# LEDDriver_v_7.net
KiCad netlist of a schematic drawn in EAGLE
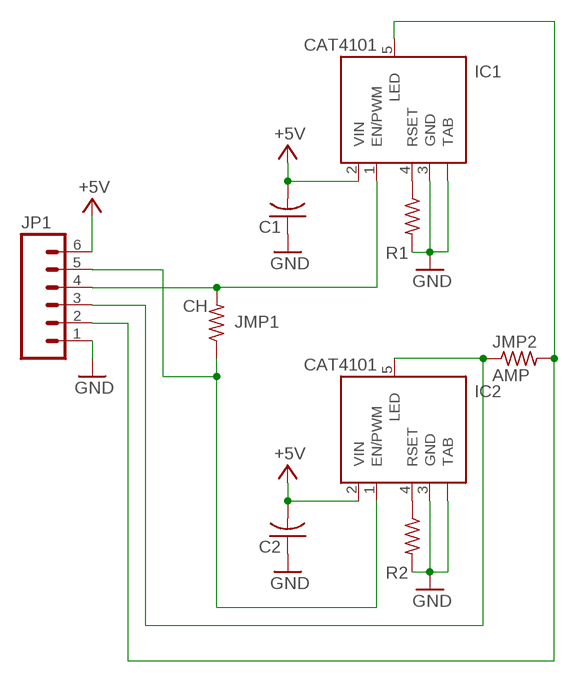
[diagram p0: schematic, sheet 1]

(export (version "E")
  (design (tool "Eeschema 10.0.6"))
  (components
    (comp (ref "C1")
      (value "C-USC1206")
      (footprint "eagle-import:C1206")
      (libsource (lib "eagle-import") (part "C-USC1206"))
    )
    (comp (ref "C2")
      (value "C-USC1206")
      (footprint "eagle-import:C1206")
      (libsource (lib "eagle-import") (part "C-USC1206"))
    )
    (comp (ref "IC1")
      (value "CAT4101")
      (footprint "eagle-import:TO263_5")
      (fields (field (name "MPN") "CAT4101TV-T75"))
      (libsource (lib "eagle-import") (part "CAT4101"))
    )
    (comp (ref "IC2")
      (value "CAT4101")
      (footprint "eagle-import:TO263_5")
      (fields (field (name "MPN") "CAT4101TV-T75"))
      (libsource (lib "eagle-import") (part "CAT4101"))
    )
    (comp (ref "JMP1")
      (value "CH")
      (footprint "eagle-import:R1206")
      (libsource (lib "eagle-import") (part "R-US_R1206"))
    )
    (comp (ref "JMP2")
      (value "AMP")
      (footprint "eagle-import:R1206")
      (libsource (lib "eagle-import") (part "R-US_R1206"))
    )
    (comp (ref "JP1")
      (value "M06LOCK_LONGPADS")
      (footprint "eagle-import:1X06_LOCK_LONGPADS")
      (libsource (lib "eagle-import") (part "M06LOCK_LONGPADS"))
    )
    (comp (ref "R1")
      (value "R-US_R1206")
      (footprint "eagle-import:R1206")
      (libsource (lib "eagle-import") (part "R-US_R1206"))
    )
    (comp (ref "R2")
      (value "R-US_R1206")
      (footprint "eagle-import:R1206")
      (libsource (lib "eagle-import") (part "R-US_R1206"))
    )
  )
  (nets
    (net (code "1") (name "+5V") (class "Default")
      (node (ref "C1") (pin "2") (pinfunction "2_2") (pintype "passive"))
      (node (ref "C2") (pin "2") (pinfunction "2_2") (pintype "passive"))
      (node (ref "IC1") (pin "2") (pinfunction "VIN_2") (pintype "input"))
      (node (ref "IC2") (pin "2") (pinfunction "VIN_2") (pintype "input"))
      (node (ref "JP1") (pin "6") (pinfunction "6_6") (pintype "passive"))
    )
    (net (code "2") (name "GND") (class "Default")
      (node (ref "C1") (pin "1") (pinfunction "1_1") (pintype "passive"))
      (node (ref "C2") (pin "1") (pinfunction "1_1") (pintype "passive"))
      (node (ref "IC1") (pin "3") (pinfunction "GND_3") (pintype "power_in"))
      (node (ref "IC1") (pin "TAB") (pinfunction "TAB_TAB") (pintype "passive"))
      (node (ref "IC2") (pin "3") (pinfunction "GND_3") (pintype "power_in"))
      (node (ref "IC2") (pin "TAB") (pinfunction "TAB_TAB") (pintype "passive"))
      (node (ref "JP1") (pin "1") (pinfunction "1_1") (pintype "passive"))
      (node (ref "R1") (pin "2") (pinfunction "2_2") (pintype "passive"))
      (node (ref "R2") (pin "2") (pinfunction "2_2") (pintype "passive"))
    )
    (net (code "3") (name "Net-(IC1-EN{slash}PWM)") (class "Default")
      (node (ref "IC1") (pin "1") (pinfunction "EN/PWM_1") (pintype "input"))
      (node (ref "JMP1") (pin "2") (pinfunction "2_2") (pintype "passive"))
      (node (ref "JP1") (pin "4") (pinfunction "4_4") (pintype "passive"))
    )
    (net (code "4") (name "Net-(IC1-LED)") (class "Default")
      (node (ref "IC1") (pin "5") (pinfunction "LED_5") (pintype "power_in"))
      (node (ref "JMP2") (pin "2") (pinfunction "2_2") (pintype "passive"))
      (node (ref "JP1") (pin "2") (pinfunction "2_2") (pintype "passive"))
    )
    (net (code "5") (name "Net-(IC1-RSET)") (class "Default")
      (node (ref "IC1") (pin "4") (pinfunction "RSET_4") (pintype "input"))
      (node (ref "R1") (pin "1") (pinfunction "1_1") (pintype "passive"))
    )
    (net (code "6") (name "Net-(IC2-EN{slash}PWM)") (class "Default")
      (node (ref "IC2") (pin "1") (pinfunction "EN/PWM_1") (pintype "input"))
      (node (ref "JMP1") (pin "1") (pinfunction "1_1") (pintype "passive"))
      (node (ref "JP1") (pin "5") (pinfunction "5_5") (pintype "passive"))
    )
    (net (code "7") (name "Net-(IC2-LED)") (class "Default")
      (node (ref "IC2") (pin "5") (pinfunction "LED_5") (pintype "power_in"))
      (node (ref "JMP2") (pin "1") (pinfunction "1_1") (pintype "passive"))
      (node (ref "JP1") (pin "3") (pinfunction "3_3") (pintype "passive"))
    )
    (net (code "8") (name "Net-(IC2-RSET)") (class "Default")
      (node (ref "IC2") (pin "4") (pinfunction "RSET_4") (pintype "input"))
      (node (ref "R2") (pin "1") (pinfunction "1_1") (pintype "passive"))
    )
  )
)
